# Adafruit_HaD_Proto_HAT_rev_A.net
KiCad netlist of a schematic drawn in EAGLE
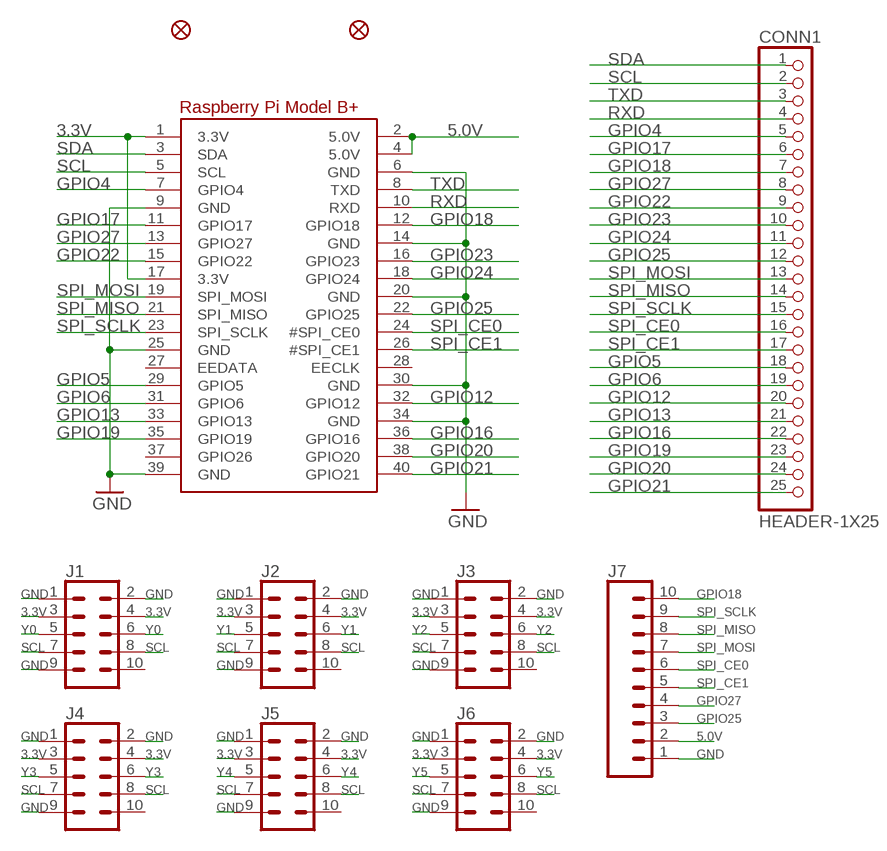
[diagram p0: schematic, sheet 1]

(export (version "E")
  (design (tool "Eeschema 10.0.6"))
  (components
    (comp (ref "CONN1")
      (value "HEADER-1X25")
      (footprint "eagle-import:1X25_ROUND_70MIL")
      (libsource (lib "eagle-import") (part "HEADER-1X25"))
    )
    (comp (ref "FID2")
      (value "FIDUCIAL\"\"")
      (footprint "eagle-import:FIDUCIAL_1MM")
      (libsource (lib "eagle-import") (part "FIDUCIAL{dblquote}{dblquote}"))
    )
    (comp (ref "FID3")
      (value "FIDUCIAL\"\"")
      (footprint "eagle-import:FIDUCIAL_1MM")
      (libsource (lib "eagle-import") (part "FIDUCIAL{dblquote}{dblquote}"))
    )
    (comp (ref "J1")
      (value "CONN_05X2SHD")
      (footprint "eagle-import:2X5-SHROUDED")
      (libsource (lib "eagle-import") (part "CONN_05X2SHD"))
    )
    (comp (ref "J2")
      (value "CONN_05X2SHD")
      (footprint "eagle-import:2X5-SHROUDED")
      (libsource (lib "eagle-import") (part "CONN_05X2SHD"))
    )
    (comp (ref "J3")
      (value "CONN_05X2SHD")
      (footprint "eagle-import:2X5-SHROUDED")
      (libsource (lib "eagle-import") (part "CONN_05X2SHD"))
    )
    (comp (ref "J4")
      (value "CONN_05X2SHD")
      (footprint "eagle-import:2X5-SHROUDED")
      (libsource (lib "eagle-import") (part "CONN_05X2SHD"))
    )
    (comp (ref "J5")
      (value "CONN_05X2SHD")
      (footprint "eagle-import:2X5-SHROUDED")
      (libsource (lib "eagle-import") (part "CONN_05X2SHD"))
    )
    (comp (ref "J6")
      (value "CONN_05X2SHD")
      (footprint "eagle-import:2X5-SHROUDED")
      (libsource (lib "eagle-import") (part "CONN_05X2SHD"))
    )
    (comp (ref "J7")
      (value "CONN_10LOCK")
      (footprint "eagle-import:1X10_LOCK")
      (libsource (lib "eagle-import") (part "CONN_10LOCK"))
    )
    (comp (ref "RPI1")
      (value "RASPBERRYPI_BPLUS_HATNOSLOTS")
      (footprint "eagle-import:PI_HAT_NOSLOTS")
      (libsource (lib "eagle-import") (part "RASPBERRYPI_BPLUS_HATNOSLOTS"))
    )
  )
  (nets
    (net (code "1") (name "/3.3V") (class "Default")
      (node (ref "J1") (pin "3") (pinfunction "3_3") (pintype "passive"))
      (node (ref "J1") (pin "4") (pinfunction "4_4") (pintype "passive"))
      (node (ref "J2") (pin "3") (pinfunction "3_3") (pintype "passive"))
      (node (ref "J2") (pin "4") (pinfunction "4_4") (pintype "passive"))
      (node (ref "J3") (pin "3") (pinfunction "3_3") (pintype "passive"))
      (node (ref "J3") (pin "4") (pinfunction "4_4") (pintype "passive"))
      (node (ref "J4") (pin "3") (pinfunction "3_3") (pintype "passive"))
      (node (ref "J4") (pin "4") (pinfunction "4_4") (pintype "passive"))
      (node (ref "J5") (pin "3") (pinfunction "3_3") (pintype "passive"))
      (node (ref "J5") (pin "4") (pinfunction "4_4") (pintype "passive"))
      (node (ref "J6") (pin "3") (pinfunction "3_3") (pintype "passive"))
      (node (ref "J6") (pin "4") (pinfunction "4_4") (pintype "passive"))
      (node (ref "RPI1") (pin "1") (pinfunction "3.3V_1") (pintype "power_in"))
      (node (ref "RPI1") (pin "17") (pinfunction "3.3V_17") (pintype "power_in"))
    )
    (net (code "2") (name "/5.0V") (class "Default")
      (node (ref "J7") (pin "2") (pinfunction "2_2") (pintype "passive"))
      (node (ref "RPI1") (pin "2") (pinfunction "5.0V_2") (pintype "power_in"))
      (node (ref "RPI1") (pin "4") (pinfunction "5.0V_4") (pintype "power_in"))
    )
    (net (code "3") (name "/EECLK") (class "Default")
      (node (ref "RPI1") (pin "28") (pinfunction "EECLK_28") (pintype "power_in"))
    )
    (net (code "4") (name "/GPIO4") (class "Default")
      (node (ref "CONN1") (pin "5") (pinfunction "5_5") (pintype "passive"))
      (node (ref "RPI1") (pin "7") (pinfunction "GPIO4_7") (pintype "bidirectional"))
    )
    (net (code "5") (name "/GPIO5") (class "Default")
      (node (ref "CONN1") (pin "18") (pinfunction "18_18") (pintype "passive"))
      (node (ref "RPI1") (pin "29") (pinfunction "GPIO5_29") (pintype "bidirectional"))
    )
    (net (code "6") (name "/GPIO6") (class "Default")
      (node (ref "CONN1") (pin "19") (pinfunction "19_19") (pintype "passive"))
      (node (ref "RPI1") (pin "31") (pinfunction "GPIO6_31") (pintype "power_in"))
    )
    (net (code "7") (name "/GPIO12") (class "Default")
      (node (ref "CONN1") (pin "20") (pinfunction "20_20") (pintype "passive"))
      (node (ref "RPI1") (pin "32") (pinfunction "GPIO12_32") (pintype "bidirectional"))
    )
    (net (code "8") (name "/GPIO13") (class "Default")
      (node (ref "CONN1") (pin "21") (pinfunction "21_21") (pintype "passive"))
      (node (ref "RPI1") (pin "33") (pinfunction "GPIO13_33") (pintype "bidirectional"))
    )
    (net (code "9") (name "/GPIO16") (class "Default")
      (node (ref "CONN1") (pin "22") (pinfunction "22_22") (pintype "passive"))
      (node (ref "RPI1") (pin "36") (pinfunction "GPIO16_36") (pintype "power_in"))
    )
    (net (code "10") (name "/GPIO17") (class "Default")
      (node (ref "CONN1") (pin "6") (pinfunction "6_6") (pintype "passive"))
      (node (ref "RPI1") (pin "11") (pinfunction "GPIO17_11") (pintype "bidirectional"))
    )
    (net (code "11") (name "/GPIO18") (class "Default")
      (node (ref "CONN1") (pin "7") (pinfunction "7_7") (pintype "passive"))
      (node (ref "J7") (pin "10") (pinfunction "10_10") (pintype "passive"))
      (node (ref "RPI1") (pin "12") (pinfunction "GPIO18_12") (pintype "bidirectional"))
    )
    (net (code "12") (name "/GPIO19") (class "Default")
      (node (ref "CONN1") (pin "23") (pinfunction "23_23") (pintype "passive"))
      (node (ref "RPI1") (pin "35") (pinfunction "GPIO19_35") (pintype "bidirectional"))
    )
    (net (code "13") (name "/GPIO20") (class "Default")
      (node (ref "CONN1") (pin "24") (pinfunction "24_24") (pintype "passive"))
      (node (ref "RPI1") (pin "38") (pinfunction "GPIO20_38") (pintype "bidirectional"))
    )
    (net (code "14") (name "/GPIO21") (class "Default")
      (node (ref "CONN1") (pin "25") (pinfunction "25_25") (pintype "passive"))
      (node (ref "RPI1") (pin "40") (pinfunction "GPIO21_40") (pintype "bidirectional"))
    )
    (net (code "15") (name "/GPIO22") (class "Default")
      (node (ref "CONN1") (pin "9") (pinfunction "9_9") (pintype "passive"))
      (node (ref "RPI1") (pin "15") (pinfunction "GPIO22_15") (pintype "bidirectional"))
    )
    (net (code "16") (name "/GPIO23") (class "Default")
      (node (ref "CONN1") (pin "10") (pinfunction "10_10") (pintype "passive"))
      (node (ref "RPI1") (pin "16") (pinfunction "GPIO23_16") (pintype "bidirectional"))
    )
    (net (code "17") (name "/GPIO24") (class "Default")
      (node (ref "CONN1") (pin "11") (pinfunction "11_11") (pintype "passive"))
      (node (ref "RPI1") (pin "18") (pinfunction "GPIO24_18") (pintype "bidirectional"))
    )
    (net (code "18") (name "/GPIO25") (class "Default")
      (node (ref "CONN1") (pin "12") (pinfunction "12_12") (pintype "passive"))
      (node (ref "J7") (pin "3") (pinfunction "3_3") (pintype "passive"))
      (node (ref "RPI1") (pin "22") (pinfunction "GPIO25_22") (pintype "bidirectional"))
    )
    (net (code "19") (name "/GPIO27") (class "Default")
      (node (ref "CONN1") (pin "8") (pinfunction "8_8") (pintype "passive"))
      (node (ref "J7") (pin "4") (pinfunction "4_4") (pintype "passive"))
      (node (ref "RPI1") (pin "13") (pinfunction "GPIO27_13") (pintype "bidirectional"))
    )
    (net (code "20") (name "/RXD") (class "Default")
      (node (ref "CONN1") (pin "4") (pinfunction "4_4") (pintype "passive"))
      (node (ref "RPI1") (pin "10") (pinfunction "RXD_10") (pintype "bidirectional"))
    )
    (net (code "21") (name "/SCL") (class "Default")
      (node (ref "CONN1") (pin "2") (pinfunction "2_2") (pintype "passive"))
      (node (ref "J1") (pin "7") (pinfunction "7_7") (pintype "passive"))
      (node (ref "J1") (pin "8") (pinfunction "8_8") (pintype "passive"))
      (node (ref "J2") (pin "7") (pinfunction "7_7") (pintype "passive"))
      (node (ref "J2") (pin "8") (pinfunction "8_8") (pintype "passive"))
      (node (ref "J3") (pin "7") (pinfunction "7_7") (pintype "passive"))
      (node (ref "J3") (pin "8") (pinfunction "8_8") (pintype "passive"))
      (node (ref "J4") (pin "7") (pinfunction "7_7") (pintype "passive"))
      (node (ref "J4") (pin "8") (pinfunction "8_8") (pintype "passive"))
      (node (ref "J5") (pin "7") (pinfunction "7_7") (pintype "passive"))
      (node (ref "J5") (pin "8") (pinfunction "8_8") (pintype "passive"))
      (node (ref "J6") (pin "7") (pinfunction "7_7") (pintype "passive"))
      (node (ref "J6") (pin "8") (pinfunction "8_8") (pintype "passive"))
      (node (ref "RPI1") (pin "5") (pinfunction "SCL_5") (pintype "bidirectional"))
    )
    (net (code "22") (name "/SDA") (class "Default")
      (node (ref "CONN1") (pin "1") (pinfunction "1_1") (pintype "passive"))
      (node (ref "RPI1") (pin "3") (pinfunction "SDA_3") (pintype "bidirectional"))
    )
    (net (code "23") (name "/SPI_CE0") (class "Default")
      (node (ref "CONN1") (pin "16") (pinfunction "16_16") (pintype "passive"))
      (node (ref "J7") (pin "6") (pinfunction "6_6") (pintype "passive"))
      (node (ref "RPI1") (pin "24") (pinfunction "#SPI_CE0_24") (pintype "bidirectional"))
    )
    (net (code "24") (name "/SPI_CE1") (class "Default")
      (node (ref "CONN1") (pin "17") (pinfunction "17_17") (pintype "passive"))
      (node (ref "J7") (pin "5") (pinfunction "5_5") (pintype "passive"))
      (node (ref "RPI1") (pin "26") (pinfunction "#SPI_CE1_26") (pintype "bidirectional"))
    )
    (net (code "25") (name "/SPI_MISO") (class "Default")
      (node (ref "CONN1") (pin "14") (pinfunction "14_14") (pintype "passive"))
      (node (ref "J7") (pin "8") (pinfunction "8_8") (pintype "passive"))
      (node (ref "RPI1") (pin "21") (pinfunction "SPI_MISO_21") (pintype "bidirectional"))
    )
    (net (code "26") (name "/SPI_MOSI") (class "Default")
      (node (ref "CONN1") (pin "13") (pinfunction "13_13") (pintype "passive"))
      (node (ref "J7") (pin "7") (pinfunction "7_7") (pintype "passive"))
      (node (ref "RPI1") (pin "19") (pinfunction "SPI_MOSI_19") (pintype "bidirectional"))
    )
    (net (code "27") (name "/SPI_SCLK") (class "Default")
      (node (ref "CONN1") (pin "15") (pinfunction "15_15") (pintype "passive"))
      (node (ref "J7") (pin "9") (pinfunction "9_9") (pintype "passive"))
      (node (ref "RPI1") (pin "23") (pinfunction "SPI_SCLK_23") (pintype "bidirectional"))
    )
    (net (code "28") (name "/TXD") (class "Default")
      (node (ref "CONN1") (pin "3") (pinfunction "3_3") (pintype "passive"))
      (node (ref "RPI1") (pin "8") (pinfunction "TXD_8") (pintype "output"))
    )
    (net (code "29") (name "/Y0") (class "Default")
      (node (ref "J1") (pin "5") (pinfunction "5_5") (pintype "passive"))
      (node (ref "J1") (pin "6") (pinfunction "6_6") (pintype "passive"))
    )
    (net (code "30") (name "/Y1") (class "Default")
      (node (ref "J2") (pin "5") (pinfunction "5_5") (pintype "passive"))
      (node (ref "J2") (pin "6") (pinfunction "6_6") (pintype "passive"))
    )
    (net (code "31") (name "/Y2") (class "Default")
      (node (ref "J3") (pin "5") (pinfunction "5_5") (pintype "passive"))
      (node (ref "J3") (pin "6") (pinfunction "6_6") (pintype "passive"))
    )
    (net (code "32") (name "/Y3") (class "Default")
      (node (ref "J4") (pin "5") (pinfunction "5_5") (pintype "passive"))
      (node (ref "J4") (pin "6") (pinfunction "6_6") (pintype "passive"))
    )
    (net (code "33") (name "/Y4") (class "Default")
      (node (ref "J5") (pin "5") (pinfunction "5_5") (pintype "passive"))
      (node (ref "J5") (pin "6") (pinfunction "6_6") (pintype "passive"))
    )
    (net (code "34") (name "/Y5") (class "Default")
      (node (ref "J6") (pin "5") (pinfunction "5_5") (pintype "passive"))
      (node (ref "J6") (pin "6") (pinfunction "6_6") (pintype "passive"))
    )
    (net (code "35") (name "GND") (class "Default")
      (node (ref "J1") (pin "1") (pinfunction "1_1") (pintype "passive"))
      (node (ref "J1") (pin "2") (pinfunction "2_2") (pintype "passive"))
      (node (ref "J1") (pin "9") (pinfunction "9_9") (pintype "passive"))
      (node (ref "J2") (pin "1") (pinfunction "1_1") (pintype "passive"))
      (node (ref "J2") (pin "2") (pinfunction "2_2") (pintype "passive"))
      (node (ref "J2") (pin "9") (pinfunction "9_9") (pintype "passive"))
      (node (ref "J3") (pin "1") (pinfunction "1_1") (pintype "passive"))
      (node (ref "J3") (pin "2") (pinfunction "2_2") (pintype "passive"))
      (node (ref "J3") (pin "9") (pinfunction "9_9") (pintype "passive"))
      (node (ref "J4") (pin "1") (pinfunction "1_1") (pintype "passive"))
      (node (ref "J4") (pin "2") (pinfunction "2_2") (pintype "passive"))
      (node (ref "J4") (pin "9") (pinfunction "9_9") (pintype "passive"))
      (node (ref "J5") (pin "1") (pinfunction "1_1") (pintype "passive"))
      (node (ref "J5") (pin "2") (pinfunction "2_2") (pintype "passive"))
      (node (ref "J5") (pin "9") (pinfunction "9_9") (pintype "passive"))
      (node (ref "J6") (pin "1") (pinfunction "1_1") (pintype "passive"))
      (node (ref "J6") (pin "2") (pinfunction "2_2") (pintype "passive"))
      (node (ref "J6") (pin "9") (pinfunction "9_9") (pintype "passive"))
      (node (ref "J7") (pin "1") (pinfunction "1_1") (pintype "passive"))
      (node (ref "RPI1") (pin "14") (pinfunction "GND_14") (pintype "power_in"))
      (node (ref "RPI1") (pin "20") (pinfunction "GND_20") (pintype "power_in"))
      (node (ref "RPI1") (pin "25") (pinfunction "GND_25") (pintype "power_in"))
      (node (ref "RPI1") (pin "30") (pinfunction "GND_30") (pintype "bidirectional"))
      (node (ref "RPI1") (pin "34") (pinfunction "GND_34") (pintype "bidirectional"))
      (node (ref "RPI1") (pin "39") (pinfunction "GND_39") (pintype "power_in"))
      (node (ref "RPI1") (pin "6") (pinfunction "GND_6") (pintype "power_in"))
      (node (ref "RPI1") (pin "9") (pinfunction "GND_9") (pintype "power_in"))
    )
    (net (code "36") (name "unconnected-(J1-Pad10)") (class "Default")
      (node (ref "J1") (pin "10") (pinfunction "10_10") (pintype "passive"))
    )
    (net (code "37") (name "unconnected-(J2-Pad10)") (class "Default")
      (node (ref "J2") (pin "10") (pinfunction "10_10") (pintype "passive"))
    )
    (net (code "38") (name "unconnected-(J3-Pad10)") (class "Default")
      (node (ref "J3") (pin "10") (pinfunction "10_10") (pintype "passive"))
    )
    (net (code "39") (name "unconnected-(J4-Pad10)") (class "Default")
      (node (ref "J4") (pin "10") (pinfunction "10_10") (pintype "passive"))
    )
    (net (code "40") (name "unconnected-(J5-Pad10)") (class "Default")
      (node (ref "J5") (pin "10") (pinfunction "10_10") (pintype "passive"))
    )
    (net (code "41") (name "unconnected-(J6-Pad10)") (class "Default")
      (node (ref "J6") (pin "10") (pinfunction "10_10") (pintype "passive"))
    )
    (net (code "42") (name "unconnected-(RPI1-EEDATA-Pad27)") (class "Default")
      (node (ref "RPI1") (pin "27") (pinfunction "EEDATA_27") (pintype "bidirectional"))
    )
    (net (code "43") (name "unconnected-(RPI1-GPIO26-Pad37)") (class "Default")
      (node (ref "RPI1") (pin "37") (pinfunction "GPIO26_37") (pintype "bidirectional"))
    )
  )
)
